# PCB-TCH-CON.net
KiCad netlist of a schematic drawn in EAGLE
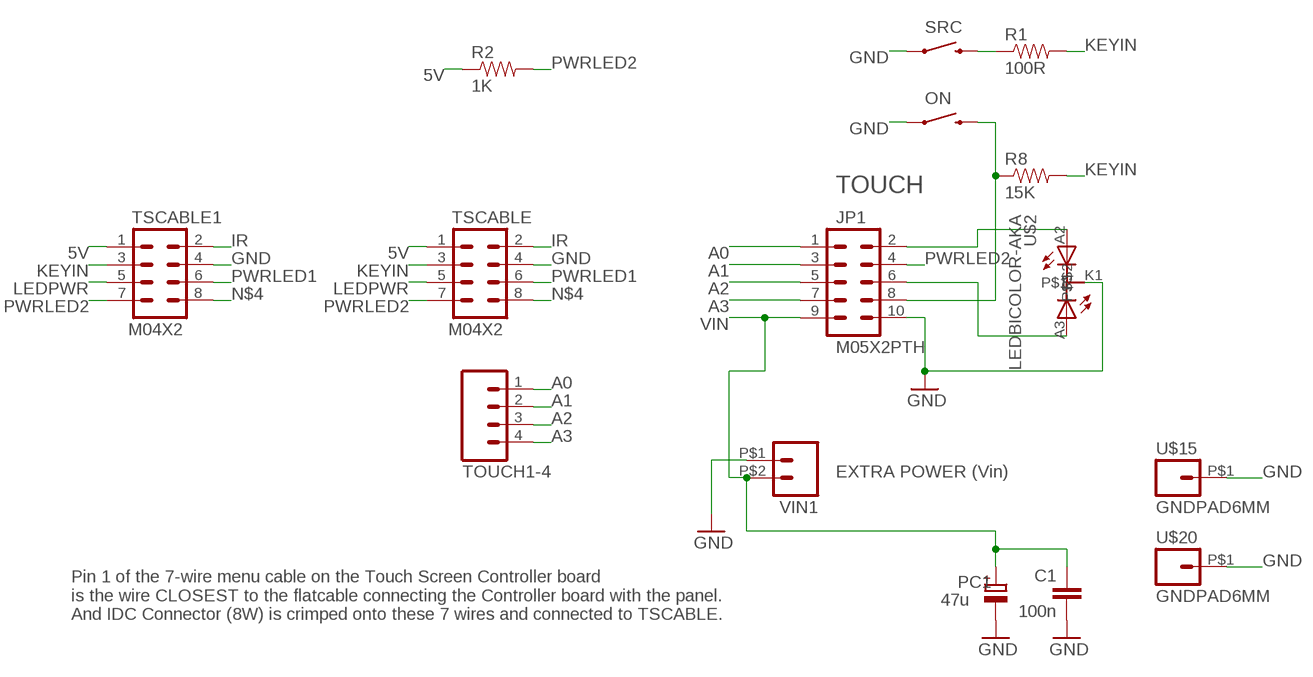
[diagram p0: schematic, sheet 1]

(export (version "E")
  (design (tool "Eeschema 10.0.6"))
  (components
    (comp (ref "C1")
      (value "100n")
      (footprint "eagle-import:C0603-ROUND")
      (libsource (lib "eagle-import") (part "C-EU0603-RND"))
    )
    (comp (ref "JP1")
      (value "M05X2PTH")
      (footprint "eagle-import:AVR_ICSP")
      (libsource (lib "eagle-import") (part "M05X2PTH"))
    )
    (comp (ref "ON")
      (value "SWITCH-MOMENTARY-2")
      (footprint "eagle-import:TACTILE_SWITCH_TALL")
      (libsource (lib "eagle-import") (part "SWITCH-MOMENTARY-2"))
    )
    (comp (ref "PC1")
      (value "47u")
      (footprint "eagle-import:PANASONIC_D")
      (libsource (lib "eagle-import") (part "CPOL-EUD"))
    )
    (comp (ref "R1")
      (value "100R")
      (footprint "eagle-import:0603-RES")
      (libsource (lib "eagle-import") (part "RESISTOR0603-RES"))
    )
    (comp (ref "R2")
      (value "1K")
      (footprint "eagle-import:0603-RES")
      (libsource (lib "eagle-import") (part "RESISTOR0603-RES"))
    )
    (comp (ref "R8")
      (value "15K")
      (footprint "eagle-import:0603-RES")
      (libsource (lib "eagle-import") (part "RESISTOR0603-RES"))
    )
    (comp (ref "SRC")
      (value "SWITCH-MOMENTARY-2")
      (footprint "eagle-import:TACTILE_SWITCH_TALL")
      (libsource (lib "eagle-import") (part "SWITCH-MOMENTARY-2"))
    )
    (comp (ref "TOUCH1-4")
      (value "M04PTH")
      (footprint "eagle-import:1X04")
      (libsource (lib "eagle-import") (part "M04PTH"))
    )
    (comp (ref "TSCABLE")
      (value "M04X2")
      (footprint "eagle-import:2X4")
      (libsource (lib "eagle-import") (part "M04X2"))
    )
    (comp (ref "TSCABLE1")
      (value "M04X2")
      (footprint "eagle-import:2X4")
      (libsource (lib "eagle-import") (part "M04X2"))
    )
    (comp (ref "U$2")
      (value "LEDBICOLOR-AKA")
      (footprint "eagle-import:LED5MM-BICOLOR")
      (libsource (lib "eagle-import") (part "LEDBICOLOR-AKA"))
    )
    (comp (ref "U$15")
      (value "GNDPAD6MM")
      (footprint "eagle-import:3.2MMPAD6MM")
      (libsource (lib "eagle-import") (part "GNDPAD6MM"))
    )
    (comp (ref "U$20")
      (value "GNDPAD6MM")
      (footprint "eagle-import:3.2MMPAD6MM")
      (libsource (lib "eagle-import") (part "GNDPAD6MM"))
    )
    (comp (ref "VIN1")
      (value "M02PTH2")
      (footprint "eagle-import:1X02_BIG")
      (libsource (lib "eagle-import") (part "M02PTH2"))
    )
  )
  (nets
    (net (code "1") (name "/5V") (class "Default")
      (node (ref "R2") (pin "1") (pinfunction "1_1") (pintype "passive"))
      (node (ref "TSCABLE") (pin "1") (pinfunction "1_1") (pintype "passive"))
      (node (ref "TSCABLE1") (pin "1") (pinfunction "1_1") (pintype "passive"))
    )
    (net (code "2") (name "/A0") (class "Default")
      (node (ref "JP1") (pin "1") (pinfunction "1_1") (pintype "passive"))
      (node (ref "TOUCH1-4") (pin "1") (pinfunction "1_1") (pintype "passive"))
    )
    (net (code "3") (name "/A1") (class "Default")
      (node (ref "JP1") (pin "3") (pinfunction "3_3") (pintype "passive"))
      (node (ref "TOUCH1-4") (pin "2") (pinfunction "2_2") (pintype "passive"))
    )
    (net (code "4") (name "/A2") (class "Default")
      (node (ref "JP1") (pin "5") (pinfunction "5_5") (pintype "passive"))
      (node (ref "TOUCH1-4") (pin "3") (pinfunction "3_3") (pintype "passive"))
    )
    (net (code "5") (name "/A3") (class "Default")
      (node (ref "JP1") (pin "7") (pinfunction "7_7") (pintype "passive"))
      (node (ref "TOUCH1-4") (pin "4") (pinfunction "4_4") (pintype "passive"))
    )
    (net (code "6") (name "/IR") (class "Default")
      (node (ref "TSCABLE") (pin "2") (pinfunction "2_2") (pintype "passive"))
      (node (ref "TSCABLE1") (pin "2") (pinfunction "2_2") (pintype "passive"))
    )
    (net (code "7") (name "/KEYIN") (class "Default")
      (node (ref "R1") (pin "2") (pinfunction "2_2") (pintype "passive"))
      (node (ref "R8") (pin "2") (pinfunction "2_2") (pintype "passive"))
      (node (ref "TSCABLE") (pin "3") (pinfunction "3_3") (pintype "passive"))
      (node (ref "TSCABLE1") (pin "3") (pinfunction "3_3") (pintype "passive"))
    )
    (net (code "8") (name "/LEDPWR") (class "Default")
      (node (ref "TSCABLE") (pin "5") (pinfunction "5_5") (pintype "passive"))
      (node (ref "TSCABLE1") (pin "5") (pinfunction "5_5") (pintype "passive"))
    )
    (net (code "9") (name "/N$4") (class "Default")
      (node (ref "TSCABLE") (pin "8") (pinfunction "8_8") (pintype "passive"))
      (node (ref "TSCABLE1") (pin "8") (pinfunction "8_8") (pintype "passive"))
    )
    (net (code "10") (name "/PWRLED1") (class "Default")
      (node (ref "TSCABLE") (pin "6") (pinfunction "6_6") (pintype "passive"))
      (node (ref "TSCABLE1") (pin "6") (pinfunction "6_6") (pintype "passive"))
    )
    (net (code "11") (name "/PWRLED2") (class "Default")
      (node (ref "JP1") (pin "4") (pinfunction "4_4") (pintype "passive"))
      (node (ref "R2") (pin "2") (pinfunction "2_2") (pintype "passive"))
      (node (ref "TSCABLE") (pin "7") (pinfunction "7_7") (pintype "passive"))
      (node (ref "TSCABLE1") (pin "7") (pinfunction "7_7") (pintype "passive"))
    )
    (net (code "12") (name "/VIN") (class "Default")
      (node (ref "C1") (pin "1") (pinfunction "1_1") (pintype "passive"))
      (node (ref "JP1") (pin "9") (pinfunction "9_9") (pintype "passive"))
      (node (ref "PC1") (pin "+") (pinfunction "+_+") (pintype "passive"))
      (node (ref "VIN1") (pin "P$2") (pinfunction "2_P$2") (pintype "passive"))
    )
    (net (code "13") (name "GND") (class "Default")
      (node (ref "C1") (pin "2") (pinfunction "2_2") (pintype "passive"))
      (node (ref "JP1") (pin "10") (pinfunction "10_10") (pintype "passive"))
      (node (ref "ON") (pin "A2") (pinfunction "1_A2") (pintype "passive"))
      (node (ref "PC1") (pin "-") (pinfunction "-_-") (pintype "passive"))
      (node (ref "SRC") (pin "A2") (pinfunction "1_A2") (pintype "passive"))
      (node (ref "TSCABLE") (pin "4") (pinfunction "4_4") (pintype "passive"))
      (node (ref "TSCABLE1") (pin "4") (pinfunction "4_4") (pintype "passive"))
      (node (ref "U$15") (pin "P$1") (pinfunction "1_P$1") (pintype "passive"))
      (node (ref "U$2") (pin "K1") (pinfunction "P$1_K1") (pintype "bidirectional"))
      (node (ref "U$20") (pin "P$1") (pinfunction "1_P$1") (pintype "passive"))
      (node (ref "VIN1") (pin "P$1") (pinfunction "1_P$1") (pintype "passive"))
    )
    (net (code "14") (name "Net-(ON-2)") (class "Default")
      (node (ref "JP1") (pin "8") (pinfunction "8_8") (pintype "passive"))
      (node (ref "ON") (pin "B2") (pinfunction "2_B2") (pintype "passive"))
      (node (ref "R8") (pin "1") (pinfunction "1_1") (pintype "passive"))
    )
    (net (code "15") (name "Net-(SRC-2)") (class "Default")
      (node (ref "R1") (pin "1") (pinfunction "1_1") (pintype "passive"))
      (node (ref "SRC") (pin "B2") (pinfunction "2_B2") (pintype "passive"))
    )
    (net (code "16") (name "Net-(U$2-P$2)") (class "Default")
      (node (ref "JP1") (pin "2") (pinfunction "2_2") (pintype "passive"))
      (node (ref "U$2") (pin "A2") (pinfunction "P$2_A2") (pintype "bidirectional"))
    )
    (net (code "17") (name "Net-(U$2-P$3)") (class "Default")
      (node (ref "JP1") (pin "6") (pinfunction "6_6") (pintype "passive"))
      (node (ref "U$2") (pin "A3") (pinfunction "P$3_A3") (pintype "bidirectional"))
    )
  )
)
